# ESD-ESP32.net
KiCad netlist of a schematic drawn in Altium Designer
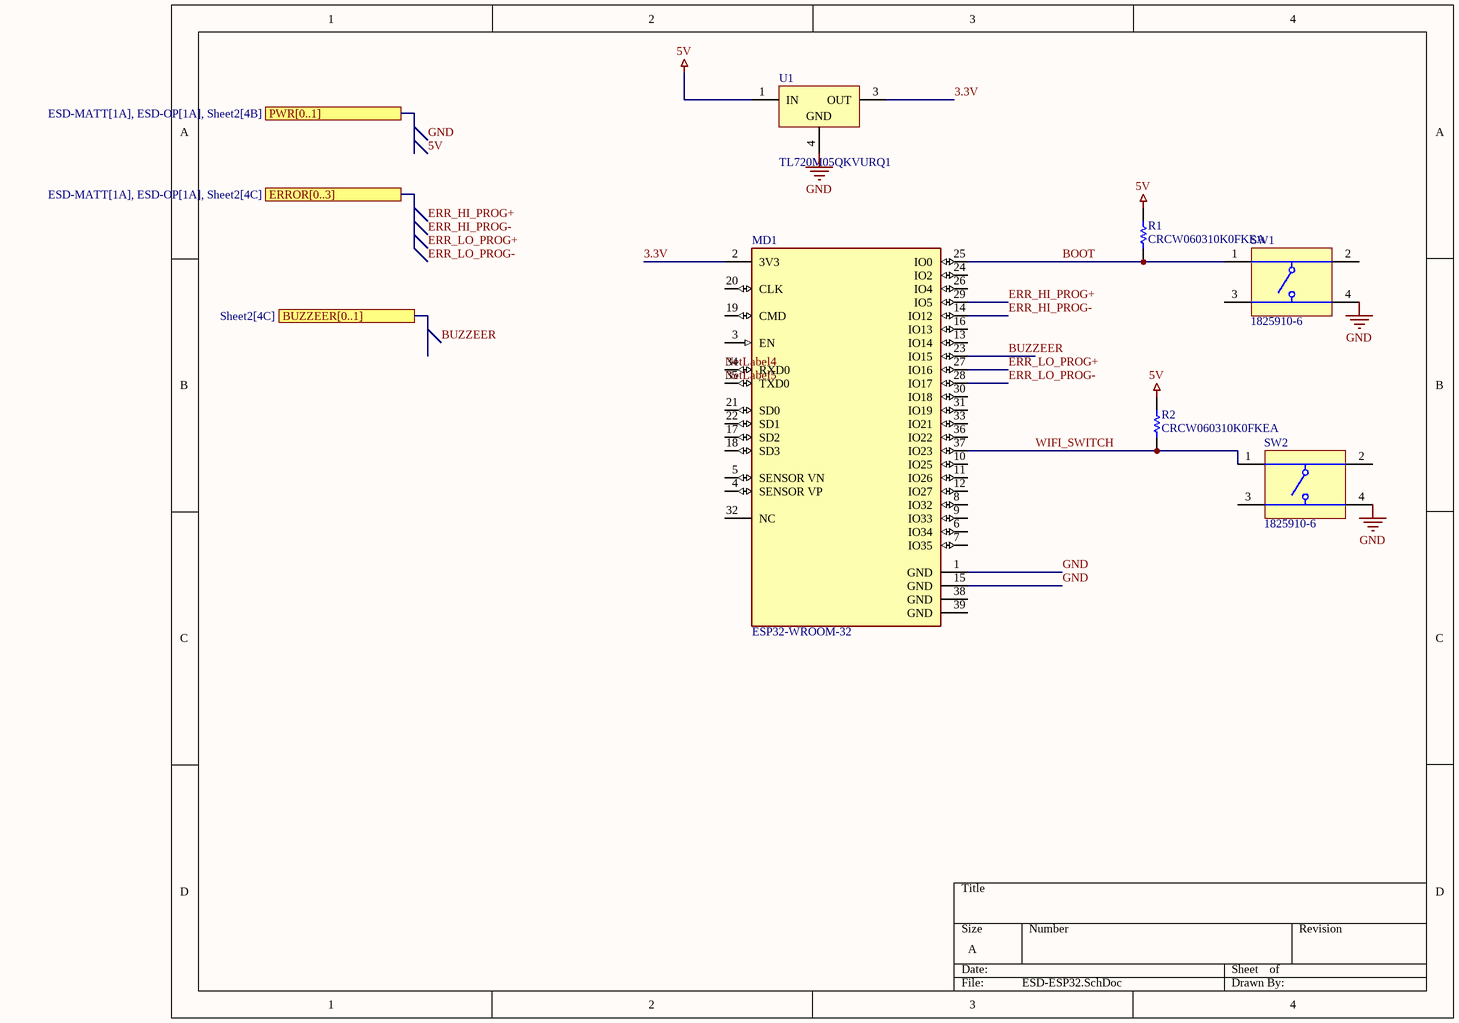
[diagram p0: ESD-ESP32.SchDoc]

(export (version "E")
  (design (tool "Eeschema 10.0.6"))
  (components
    (comp (ref "MD1")
      (value "ESP32-WROOM-32")
      (footprint "FP-ESP32-WROOM-32-MFG")
      (description "RX TXRX MOD WIFI SURFACE MOUNT")
      (libsource (lib "Altium Content Vault") (part "ee866abf0b6c51247b7f5cdebf2f250"))
    )
    (comp (ref "R1")
      (value "CRCW060310K0FKEA")
      (footprint "RESC1609X50X30NL8T20")
      (description "Chip Resistor, 10 KOhm, +/- 1%, 100 mW, -55 to 155 degC, 0603 (1608 Metric), RoHS, Tape and Reel")
      (fields (field (name "MANUFACTURER") "Vishay Semiconductor"))
      (libsource (lib "Altium Content Vault") (part "RES-2"))
    )
    (comp (ref "R2")
      (value "CRCW060310K0FKEA")
      (footprint "RESC1609X50X30NL8T20")
      (description "Chip Resistor, 10 KOhm, +/- 1%, 100 mW, -55 to 155 degC, 0603 (1608 Metric), RoHS, Tape and Reel")
      (fields (field (name "MANUFACTURER") "Vishay Semiconductor"))
      (libsource (lib "Altium Content Vault") (part "RES-2"))
    )
    (comp (ref "SW1")
      (value "1825910-6")
      (footprint "TECO-1825910-6_V")
      (description "Tact Switch, SPST-NO, 0.05 A, -35 to 85 degC, 4-Pin THD, RoHS, Bulk")
      (fields (field (name "MANUFACTURER") "TE Connectivity"))
      (libsource (lib "Altium Content Vault") (part "SW-SPST-4_A"))
    )
    (comp (ref "SW2")
      (value "1825910-6")
      (footprint "TECO-1825910-6_V")
      (description "Tact Switch, SPST-NO, 0.05 A, -35 to 85 degC, 4-Pin THD, RoHS, Bulk")
      (fields (field (name "MANUFACTURER") "TE Connectivity"))
      (libsource (lib "Altium Content Vault") (part "SW-SPST-4_A"))
    )
    (comp (ref "U1")
      (value "TL720M05QKVURQ1")
      (footprint "KVU0003A_M")
      (fields (field (name "MANUFACTURER") "Texas Instruments"))
      (libsource (lib "Altium Content Vault") (part "TI-TL7X0MXX-Q1KVU3"))
    )
  )
  (nets
    (net (code "9") (name "/3.3V") (class "Default")
      (node (ref "MD1") (pin "2") (pinfunction "3V3_2") (pintype "power_in"))
      (node (ref "U1") (pin "3") (pinfunction "OUT_3") (pintype "power_in"))
    )
    (net (code "10") (name "/BOOT") (class "Default")
      (node (ref "MD1") (pin "25") (pinfunction "IO0_25") (pintype "bidirectional"))
      (node (ref "R1") (pin "1") (pinfunction "1_1") (pintype "passive"))
      (node (ref "SW1") (pin "1") (pinfunction "1_1") (pintype "passive"))
    )
    (net (code "11") (name "/BUZZEER") (class "Default")
      (node (ref "MD1") (pin "23") (pinfunction "IO15_23") (pintype "bidirectional"))
    )
    (net (code "14") (name "/ERR_HI_PROG+") (class "Default")
      (node (ref "MD1") (pin "29") (pinfunction "IO5_29") (pintype "bidirectional"))
    )
    (net (code "15") (name "/ERR_HI_PROG-") (class "Default")
      (node (ref "MD1") (pin "14") (pinfunction "IO12_14") (pintype "bidirectional"))
    )
    (net (code "16") (name "/ERR_LO_PROG+") (class "Default")
      (node (ref "MD1") (pin "27") (pinfunction "IO16_27") (pintype "bidirectional"))
    )
    (net (code "17") (name "/ERR_LO_PROG-") (class "Default")
      (node (ref "MD1") (pin "28") (pinfunction "IO17_28") (pintype "bidirectional"))
    )
    (net (code "18") (name "/NetLabel4") (class "Default")
      (node (ref "MD1") (pin "34") (pinfunction "RXD0_34") (pintype "bidirectional"))
    )
    (net (code "19") (name "/NetLabel5") (class "Default")
      (node (ref "MD1") (pin "35") (pinfunction "TXD0_35") (pintype "bidirectional"))
    )
    (net (code "21") (name "/WIFI_SWITCH") (class "Default")
      (node (ref "MD1") (pin "37") (pinfunction "IO23_37") (pintype "bidirectional"))
      (node (ref "R2") (pin "1") (pinfunction "1_1") (pintype "passive"))
      (node (ref "SW2") (pin "1") (pinfunction "1_1") (pintype "passive"))
    )
    (net (code "22") (name "5V") (class "Default")
      (node (ref "R1") (pin "2") (pinfunction "2_2") (pintype "passive"))
      (node (ref "R2") (pin "2") (pinfunction "2_2") (pintype "passive"))
      (node (ref "U1") (pin "1") (pinfunction "IN_1") (pintype "power_in"))
    )
    (net (code "23") (name "GND") (class "Default")
      (node (ref "MD1") (pin "1") (pinfunction "GND_1") (pintype "power_in"))
      (node (ref "MD1") (pin "15") (pinfunction "GND_15") (pintype "power_in"))
      (node (ref "SW1") (pin "4") (pinfunction "4_4") (pintype "passive"))
      (node (ref "SW2") (pin "4") (pinfunction "4_4") (pintype "passive"))
      (node (ref "U1") (pin "4") (pinfunction "GND_4") (pintype "power_in"))
    )
    (net (code "24") (name "unconnected-(MD1-CLK-Pad20)") (class "Default")
      (node (ref "MD1") (pin "20") (pinfunction "CLK_20") (pintype "bidirectional"))
    )
    (net (code "25") (name "unconnected-(MD1-CMD-Pad19)") (class "Default")
      (node (ref "MD1") (pin "19") (pinfunction "CMD_19") (pintype "bidirectional"))
    )
    (net (code "26") (name "unconnected-(MD1-EN-Pad3)") (class "Default")
      (node (ref "MD1") (pin "3") (pinfunction "EN_3") (pintype "input"))
    )
    (net (code "27") (name "unconnected-(MD1-GND-Pad38)") (class "Default")
      (node (ref "MD1") (pin "38") (pinfunction "GND_38") (pintype "power_in"))
    )
    (net (code "28") (name "unconnected-(MD1-GND-Pad39)") (class "Default")
      (node (ref "MD1") (pin "39") (pinfunction "GND_39") (pintype "power_in"))
    )
    (net (code "29") (name "unconnected-(MD1-IO2-Pad24)") (class "Default")
      (node (ref "MD1") (pin "24") (pinfunction "IO2_24") (pintype "bidirectional"))
    )
    (net (code "30") (name "unconnected-(MD1-IO4-Pad26)") (class "Default")
      (node (ref "MD1") (pin "26") (pinfunction "IO4_26") (pintype "bidirectional"))
    )
    (net (code "31") (name "unconnected-(MD1-IO13-Pad16)") (class "Default")
      (node (ref "MD1") (pin "16") (pinfunction "IO13_16") (pintype "bidirectional"))
    )
    (net (code "32") (name "unconnected-(MD1-IO14-Pad13)") (class "Default")
      (node (ref "MD1") (pin "13") (pinfunction "IO14_13") (pintype "bidirectional"))
    )
    (net (code "33") (name "unconnected-(MD1-IO18-Pad30)") (class "Default")
      (node (ref "MD1") (pin "30") (pinfunction "IO18_30") (pintype "bidirectional"))
    )
    (net (code "34") (name "unconnected-(MD1-IO19-Pad31)") (class "Default")
      (node (ref "MD1") (pin "31") (pinfunction "IO19_31") (pintype "bidirectional"))
    )
    (net (code "35") (name "unconnected-(MD1-IO21-Pad33)") (class "Default")
      (node (ref "MD1") (pin "33") (pinfunction "IO21_33") (pintype "bidirectional"))
    )
    (net (code "36") (name "unconnected-(MD1-IO22-Pad36)") (class "Default")
      (node (ref "MD1") (pin "36") (pinfunction "IO22_36") (pintype "bidirectional"))
    )
    (net (code "37") (name "unconnected-(MD1-IO25-Pad10)") (class "Default")
      (node (ref "MD1") (pin "10") (pinfunction "IO25_10") (pintype "bidirectional"))
    )
    (net (code "38") (name "unconnected-(MD1-IO26-Pad11)") (class "Default")
      (node (ref "MD1") (pin "11") (pinfunction "IO26_11") (pintype "bidirectional"))
    )
    (net (code "39") (name "unconnected-(MD1-IO27-Pad12)") (class "Default")
      (node (ref "MD1") (pin "12") (pinfunction "IO27_12") (pintype "bidirectional"))
    )
    (net (code "40") (name "unconnected-(MD1-IO32-Pad8)") (class "Default")
      (node (ref "MD1") (pin "8") (pinfunction "IO32_8") (pintype "bidirectional"))
    )
    (net (code "41") (name "unconnected-(MD1-IO33-Pad9)") (class "Default")
      (node (ref "MD1") (pin "9") (pinfunction "IO33_9") (pintype "bidirectional"))
    )
    (net (code "42") (name "unconnected-(MD1-IO34-Pad6)") (class "Default")
      (node (ref "MD1") (pin "6") (pinfunction "IO34_6") (pintype "bidirectional"))
    )
    (net (code "43") (name "unconnected-(MD1-IO35-Pad7)") (class "Default")
      (node (ref "MD1") (pin "7") (pinfunction "IO35_7") (pintype "bidirectional"))
    )
    (net (code "44") (name "unconnected-(MD1-NC-Pad32)") (class "Default")
      (node (ref "MD1") (pin "32") (pinfunction "NC_32") (pintype "passive"))
    )
    (net (code "45") (name "unconnected-(MD1-SD0-Pad21)") (class "Default")
      (node (ref "MD1") (pin "21") (pinfunction "SD0_21") (pintype "bidirectional"))
    )
    (net (code "46") (name "unconnected-(MD1-SD1-Pad22)") (class "Default")
      (node (ref "MD1") (pin "22") (pinfunction "SD1_22") (pintype "bidirectional"))
    )
    (net (code "47") (name "unconnected-(MD1-SD2-Pad17)") (class "Default")
      (node (ref "MD1") (pin "17") (pinfunction "SD2_17") (pintype "bidirectional"))
    )
    (net (code "48") (name "unconnected-(MD1-SD3-Pad18)") (class "Default")
      (node (ref "MD1") (pin "18") (pinfunction "SD3_18") (pintype "bidirectional"))
    )
    (net (code "49") (name "unconnected-(MD1-SENSOR_VN-Pad5)") (class "Default")
      (node (ref "MD1") (pin "5") (pinfunction "SENSOR_VN_5") (pintype "bidirectional"))
    )
    (net (code "50") (name "unconnected-(MD1-SENSOR_VP-Pad4)") (class "Default")
      (node (ref "MD1") (pin "4") (pinfunction "SENSOR_VP_4") (pintype "bidirectional"))
    )
    (net (code "51") (name "unconnected-(SW1-Pad2)") (class "Default")
      (node (ref "SW1") (pin "2") (pinfunction "2_2") (pintype "passive"))
    )
    (net (code "52") (name "unconnected-(SW1-Pad3)") (class "Default")
      (node (ref "SW1") (pin "3") (pinfunction "3_3") (pintype "passive"))
    )
    (net (code "53") (name "unconnected-(SW2-Pad2)") (class "Default")
      (node (ref "SW2") (pin "2") (pinfunction "2_2") (pintype "passive"))
    )
    (net (code "54") (name "unconnected-(SW2-Pad3)") (class "Default")
      (node (ref "SW2") (pin "3") (pinfunction "3_3") (pintype "passive"))
    )
  )
)
